# Regul.net
KiCad netlist of a schematic drawn in Altium Designer
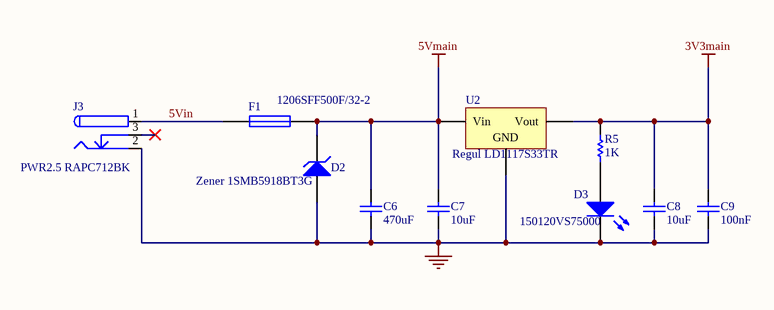
[diagram p0: Regul.SchDoc]

(export (version "E")
  (design (tool "Eeschema 10.0.6"))
  (components
    (comp (ref "C6")
      (value "470uF")
      (footprint "MarvinPcbLib2:CONDO_D_10mm")
      (description "Capacitor")
      (fields (field (name "PUBLISHER") "Altium Limited"))
      (libsource (lib "Miscellaneous Devices") (part "Cap"))
    )
    (comp (ref "C7")
      (value "10uF")
      (footprint "MarvinPcbLib2:CONDO_D_5MM")
      (description "Capacitor")
      (fields (field (name "PUBLISHER") "Altium Limited"))
      (libsource (lib "Miscellaneous Devices") (part "Cap"))
    )
    (comp (ref "C8")
      (value "10uF")
      (footprint "MarvinPcbLib2:CONDO_D_5MM")
      (description "Capacitor")
      (fields (field (name "PUBLISHER") "Altium Limited"))
      (libsource (lib "Miscellaneous Devices") (part "Cap"))
    )
    (comp (ref "C9")
      (value "100nF")
      (footprint "MarvinPcbLib2:1608 / 0603")
      (description "Capacitor")
      (fields (field (name "PUBLISHER") "Altium Limited"))
      (libsource (lib "Miscellaneous Devices") (part "Cap"))
    )
    (comp (ref "D2")
      (value "Zener 1SMB5918BT3G")
      (footprint "DIODE ZENER")
      (description "Zener Diode")
      (fields (field (name "PUBLISHER") "Altium Limited"))
      (libsource (lib "Miscellaneous Devices") (part "D Zener"))
    )
    (comp (ref "D3")
      (value "150120VS75000")
      (footprint "3216 / 1206")
      (description "Green LED")
      (fields (field (name "PUBLISHER") "Altium Limited"))
      (libsource (lib "Miscellaneous Devices") (part "LED0"))
    )
    (comp (ref "F1")
      (value "1206SFF500F/32-2")
      (footprint "3216 / 1206")
      (description "Fuse")
      (fields (field (name "PUBLISHER") "Altium Limited"))
      (libsource (lib "Miscellaneous Devices") (part "Fuse 1"))
    )
    (comp (ref "J3")
      (value "PWR2.5 RAPC712BK")
      (footprint "RAPC712BK")
      (description "Jack Connector")
      (fields (field (name "PUBLISHER") "Altium Limited"))
      (libsource (lib "Miscellaneous Connectors") (part "PWR2.5"))
    )
    (comp (ref "R5")
      (value "1K")
      (footprint "1608 / 0603")
      (description "Resistor")
      (fields (field (name "PUBLISHER") "Altium Limited"))
      (libsource (lib "Miscellaneous Devices") (part "Res1"))
    )
    (comp (ref "U2")
      (value "Regul LD1117S33TR")
      (footprint "SOT-223")
      (description "Voltage Regulator")
      (fields (field (name "PUBLISHER") "Altium Limited"))
      (libsource (lib "Miscellaneous Devices") (part "Volt Reg"))
    )
  )
  (nets
    (net (code "1") (name "/5Vin") (class "Default")
      (node (ref "F1") (pin "1") (pinfunction "1_1") (pintype "passive"))
      (node (ref "J3") (pin "1") (pinfunction "1_1") (pintype "power_in"))
    )
    (net (code "2") (name "3V3main") (class "Default")
      (node (ref "C8") (pin "2") (pinfunction "2_2") (pintype "passive"))
      (node (ref "C9") (pin "2") (pinfunction "2_2") (pintype "passive"))
      (node (ref "R5") (pin "2") (pinfunction "2_2") (pintype "passive"))
      (node (ref "U2") (pin "3") (pinfunction "Vout_3") (pintype "passive"))
    )
    (net (code "3") (name "5Vmain") (class "Default")
      (node (ref "C6") (pin "2") (pinfunction "2_2") (pintype "passive"))
      (node (ref "C7") (pin "2") (pinfunction "2_2") (pintype "passive"))
      (node (ref "D2") (pin "2") (pinfunction "K_2") (pintype "passive"))
      (node (ref "F1") (pin "2") (pinfunction "2_2") (pintype "passive"))
      (node (ref "U2") (pin "1") (pinfunction "Vin_1") (pintype "passive"))
    )
    (net (code "4") (name "GND") (class "Default")
      (node (ref "C6") (pin "1") (pinfunction "1_1") (pintype "passive"))
      (node (ref "C7") (pin "1") (pinfunction "1_1") (pintype "passive"))
      (node (ref "C8") (pin "1") (pinfunction "1_1") (pintype "passive"))
      (node (ref "C9") (pin "1") (pinfunction "1_1") (pintype "passive"))
      (node (ref "D2") (pin "1") (pinfunction "A_1") (pintype "passive"))
      (node (ref "D3") (pin "2") (pinfunction "K_2") (pintype "passive"))
      (node (ref "J3") (pin "2") (pinfunction "2_2") (pintype "power_in"))
      (node (ref "U2") (pin "2") (pinfunction "GND_2") (pintype "passive"))
    )
    (net (code "5") (name "Net-(D3-A)") (class "Default")
      (node (ref "D3") (pin "1") (pinfunction "A_1") (pintype "passive"))
      (node (ref "R5") (pin "1") (pinfunction "1_1") (pintype "passive"))
    )
    (net (code "6") (name "unconnected-(J3-Pad3)") (class "Default")
      (node (ref "J3") (pin "3") (pinfunction "3_3") (pintype "power_in+no_connect"))
    )
  )
)
